# usb_power_relay.net
KiCad netlist of a schematic drawn in EAGLE
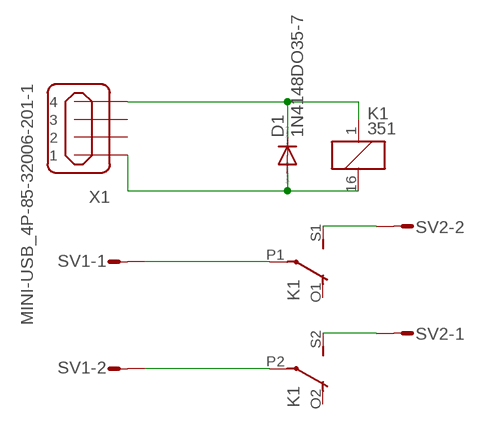
[diagram p0: schematic, sheet 1]

(export (version "E")
  (design (tool "Eeschema 10.0.6"))
  (components
    (comp (ref "D1")
      (value "1N4148DO35-7")
      (footprint "eagle-import:DO35-7")
      (libsource (lib "eagle-import") (part "1N4148DO35-7"))
    )
    (comp (ref "K1")
      (value "351")
      (footprint "eagle-import:351")
      (libsource (lib "eagle-import") (part "351"))
    )
    (comp (ref "SV1")
      (value "S02P")
      (footprint "eagle-import:S02P")
      (libsource (lib "eagle-import") (part "S02P"))
    )
    (comp (ref "SV2")
      (value "S02P")
      (footprint "eagle-import:S02P")
      (libsource (lib "eagle-import") (part "S02P"))
    )
    (comp (ref "X1")
      (value "MINI-USB_4P-85-32006-201-1")
      (footprint "eagle-import:85-32006-201-1")
      (libsource (lib "eagle-import") (part "MINI-USB_4P-85-32006-201-1"))
    )
  )
  (nets
    (net (code "1") (name "Net-(D1-PadC)") (class "Default")
      (node (ref "D1") (pin "C") (pinfunction "C_C") (pintype "passive"))
      (node (ref "K1") (pin "1") (pinfunction "1_1") (pintype "passive"))
      (node (ref "X1") (pin "4") (pinfunction "4_4") (pintype "passive"))
    )
    (net (code "2") (name "Net-(K1A-2)") (class "Default")
      (node (ref "D1") (pin "A") (pinfunction "A_A") (pintype "passive"))
      (node (ref "K1") (pin "16") (pinfunction "2_16") (pintype "passive"))
      (node (ref "X1") (pin "1") (pinfunction "1_1") (pintype "passive"))
    )
    (net (code "3") (name "Net-(K1B-P)") (class "Default")
      (node (ref "K1") (pin "P1") (pinfunction "P_P1") (pintype "passive"))
      (node (ref "SV1") (pin "1") (pinfunction "S_1") (pintype "passive"))
    )
    (net (code "4") (name "Net-(K1B-S)") (class "Default")
      (node (ref "K1") (pin "S1") (pinfunction "S_S1") (pintype "passive"))
      (node (ref "SV2") (pin "2") (pinfunction "S_2") (pintype "passive"))
    )
    (net (code "5") (name "Net-(K1C-P)") (class "Default")
      (node (ref "K1") (pin "P2") (pinfunction "P_P2") (pintype "passive"))
      (node (ref "SV1") (pin "2") (pinfunction "S_2") (pintype "passive"))
    )
    (net (code "6") (name "Net-(K1C-S)") (class "Default")
      (node (ref "K1") (pin "S2") (pinfunction "S_S2") (pintype "passive"))
      (node (ref "SV2") (pin "1") (pinfunction "S_1") (pintype "passive"))
    )
    (net (code "7") (name "unconnected-(K1B-O-PadO1)") (class "Default")
      (node (ref "K1") (pin "O1") (pinfunction "O_O1") (pintype "passive"))
    )
    (net (code "8") (name "unconnected-(K1C-O-PadO2)") (class "Default")
      (node (ref "K1") (pin "O2") (pinfunction "O_O2") (pintype "passive"))
    )
    (net (code "9") (name "unconnected-(X1-Pad2)") (class "Default")
      (node (ref "X1") (pin "2") (pinfunction "2_2") (pintype "passive"))
    )
    (net (code "10") (name "unconnected-(X1-Pad3)") (class "Default")
      (node (ref "X1") (pin "3") (pinfunction "3_3") (pintype "passive"))
    )
  )
)
